# Nowboard.net
KiCad netlist of a schematic drawn in EAGLE
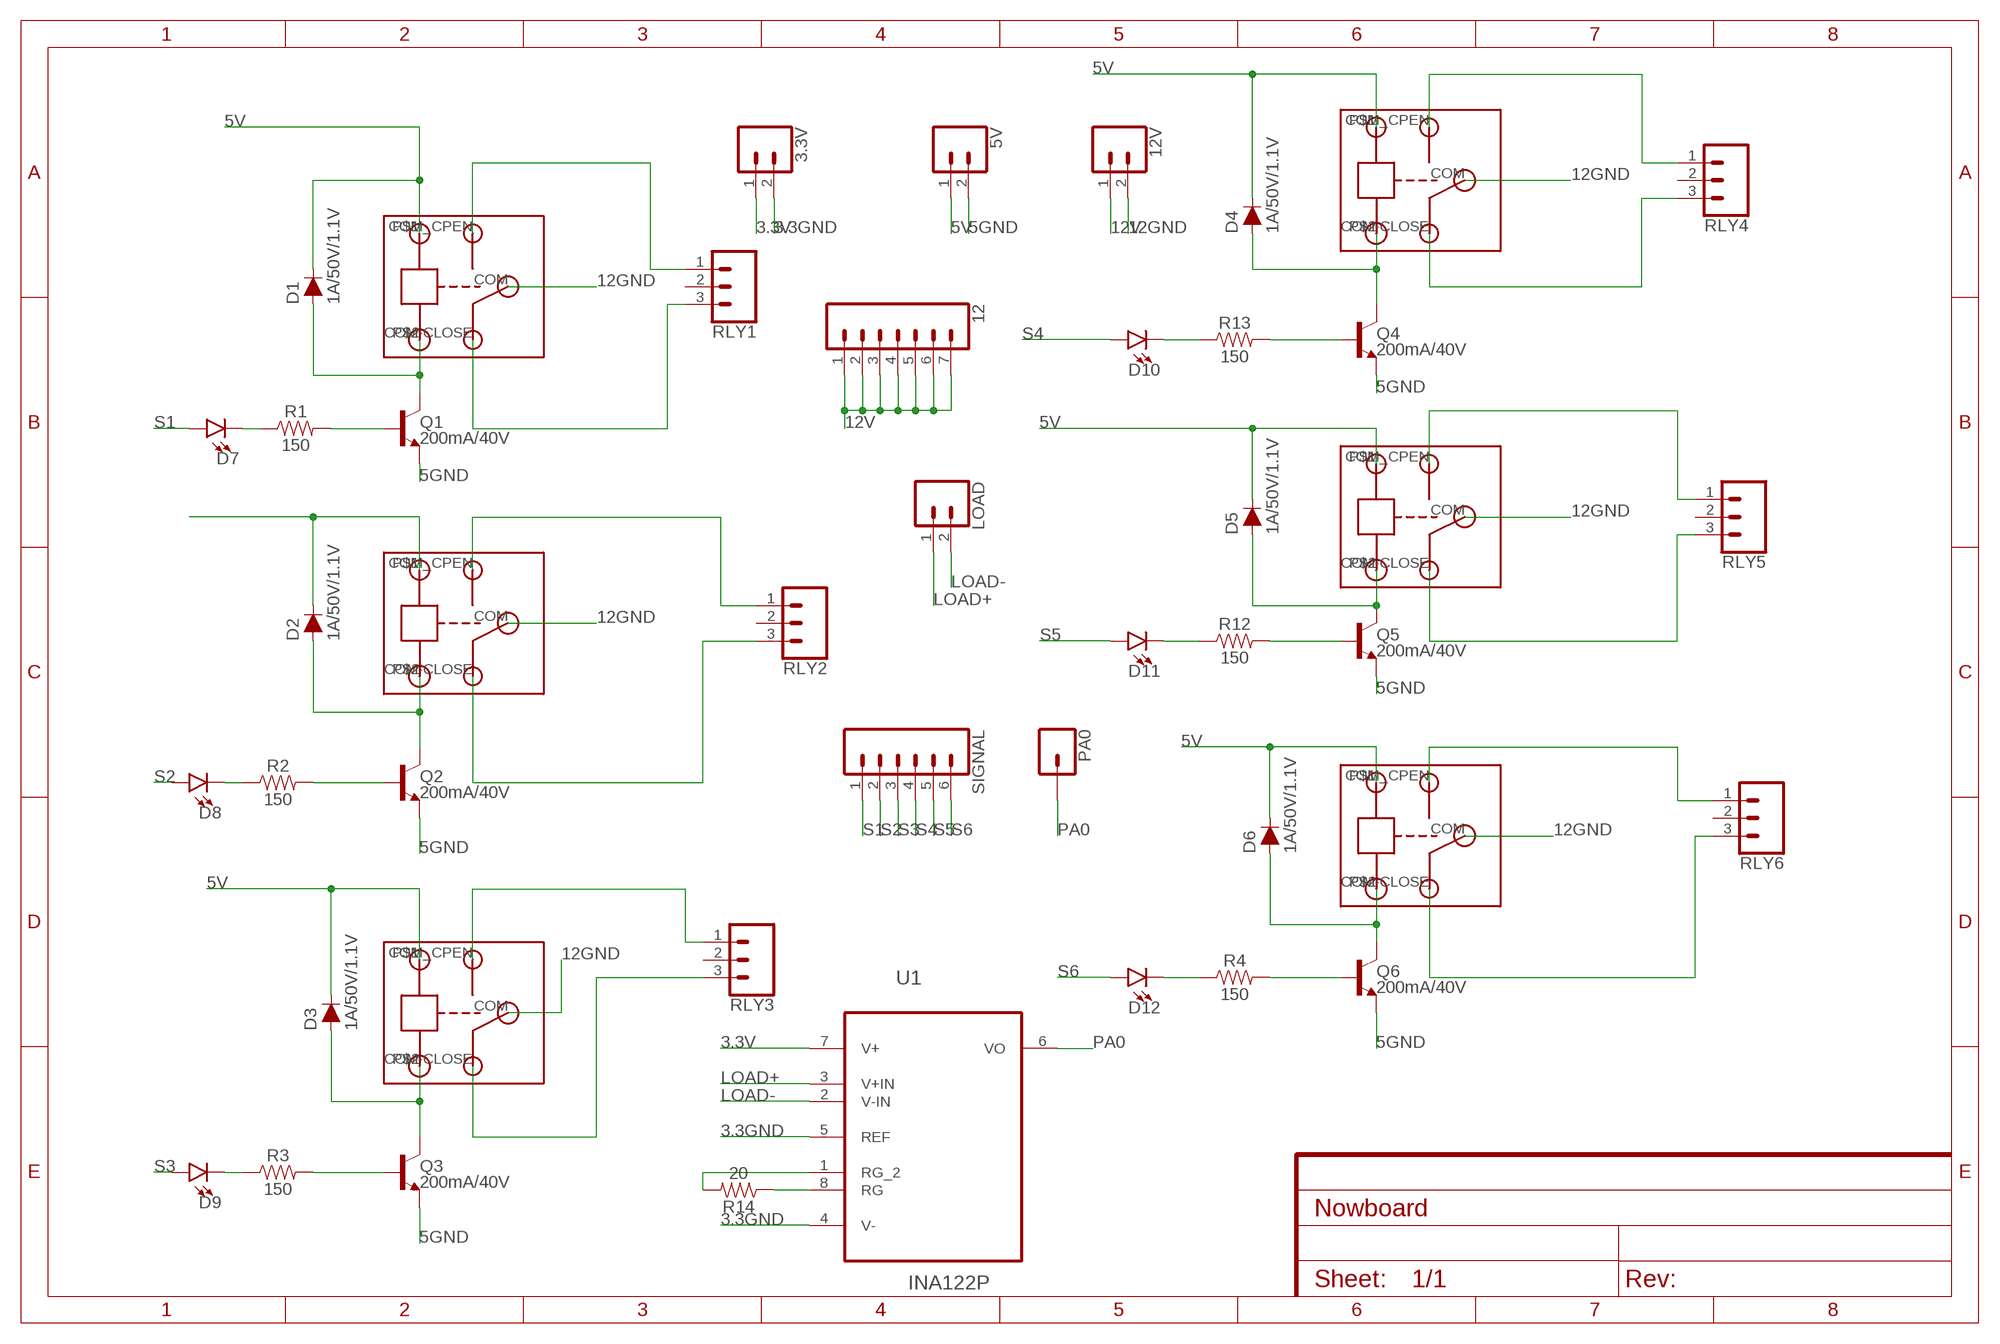
[diagram p0: schematic, sheet 1]

(export (version "E")
  (design (tool "Eeschema 10.0.6"))
  (components
    (comp (ref "3.3V")
      (value "CONN_02")
      (footprint "eagle-import:1X02")
      (libsource (lib "eagle-import") (part "CONN_02"))
    )
    (comp (ref "5V")
      (value "CONN_02")
      (footprint "eagle-import:1X02")
      (libsource (lib "eagle-import") (part "CONN_02"))
    )
    (comp (ref "12")
      (value "CONN_07")
      (footprint "eagle-import:1X07")
      (libsource (lib "eagle-import") (part "CONN_07"))
    )
    (comp (ref "12V")
      (value "CONN_02")
      (footprint "eagle-import:1X02")
      (libsource (lib "eagle-import") (part "CONN_02"))
    )
    (comp (ref "D1")
      (value "1A/50V/1.1V")
      (footprint "eagle-import:DIODE-1N4001")
      (libsource (lib "eagle-import") (part "DIODE-PTH"))
    )
    (comp (ref "D2")
      (value "1A/50V/1.1V")
      (footprint "eagle-import:DIODE-1N4001")
      (libsource (lib "eagle-import") (part "DIODE-PTH"))
    )
    (comp (ref "D3")
      (value "1A/50V/1.1V")
      (footprint "eagle-import:DIODE-1N4001")
      (libsource (lib "eagle-import") (part "DIODE-PTH"))
    )
    (comp (ref "D4")
      (value "1A/50V/1.1V")
      (footprint "eagle-import:DIODE-1N4001")
      (libsource (lib "eagle-import") (part "DIODE-PTH"))
    )
    (comp (ref "D5")
      (value "1A/50V/1.1V")
      (footprint "eagle-import:DIODE-1N4001")
      (libsource (lib "eagle-import") (part "DIODE-PTH"))
    )
    (comp (ref "D6")
      (value "1A/50V/1.1V")
      (footprint "eagle-import:DIODE-1N4001")
      (libsource (lib "eagle-import") (part "DIODE-PTH"))
    )
    (comp (ref "D7")
      (value "LED3MM")
      (footprint "eagle-import:LED_3MM")
      (libsource (lib "eagle-import") (part "LED3MM"))
    )
    (comp (ref "D8")
      (value "LED3MM")
      (footprint "eagle-import:LED_3MM")
      (libsource (lib "eagle-import") (part "LED3MM"))
    )
    (comp (ref "D9")
      (value "LED3MM")
      (footprint "eagle-import:LED_3MM")
      (libsource (lib "eagle-import") (part "LED3MM"))
    )
    (comp (ref "D10")
      (value "LED3MM")
      (footprint "eagle-import:LED_3MM")
      (libsource (lib "eagle-import") (part "LED3MM"))
    )
    (comp (ref "D11")
      (value "LED3MM")
      (footprint "eagle-import:LED_3MM")
      (libsource (lib "eagle-import") (part "LED3MM"))
    )
    (comp (ref "D12")
      (value "LED3MM")
      (footprint "eagle-import:LED_3MM")
      (libsource (lib "eagle-import") (part "LED3MM"))
    )
    (comp (ref "LOAD")
      (value "CONN_02")
      (footprint "eagle-import:1X02")
      (libsource (lib "eagle-import") (part "CONN_02"))
    )
    (comp (ref "PA0")
      (value "CONN_01")
      (footprint "eagle-import:1X01")
      (libsource (lib "eagle-import") (part "CONN_01"))
    )
    (comp (ref "Q1")
      (value "200mA/40V")
      (footprint "eagle-import:TO-92")
      (libsource (lib "eagle-import") (part "TRANS_NPN-2N3904"))
    )
    (comp (ref "Q2")
      (value "200mA/40V")
      (footprint "eagle-import:TO-92")
      (libsource (lib "eagle-import") (part "TRANS_NPN-2N3904"))
    )
    (comp (ref "Q3")
      (value "200mA/40V")
      (footprint "eagle-import:TO-92")
      (libsource (lib "eagle-import") (part "TRANS_NPN-2N3904"))
    )
    (comp (ref "Q4")
      (value "200mA/40V")
      (footprint "eagle-import:TO-92")
      (libsource (lib "eagle-import") (part "TRANS_NPN-2N3904"))
    )
    (comp (ref "Q5")
      (value "200mA/40V")
      (footprint "eagle-import:TO-92")
      (libsource (lib "eagle-import") (part "TRANS_NPN-2N3904"))
    )
    (comp (ref "Q6")
      (value "200mA/40V")
      (footprint "eagle-import:TO-92")
      (libsource (lib "eagle-import") (part "TRANS_NPN-2N3904"))
    )
    (comp (ref "R1")
      (value "150")
      (footprint "eagle-import:0603")
      (libsource (lib "eagle-import") (part "150OHM-0603-1/10W-1%"))
    )
    (comp (ref "R2")
      (value "150")
      (footprint "eagle-import:0603")
      (libsource (lib "eagle-import") (part "150OHM-0603-1/10W-1%"))
    )
    (comp (ref "R3")
      (value "150")
      (footprint "eagle-import:0603")
      (libsource (lib "eagle-import") (part "150OHM-0603-1/10W-1%"))
    )
    (comp (ref "R4")
      (value "150")
      (footprint "eagle-import:0603")
      (libsource (lib "eagle-import") (part "150OHM-0603-1/10W-1%"))
    )
    (comp (ref "R12")
      (value "150")
      (footprint "eagle-import:0603")
      (libsource (lib "eagle-import") (part "150OHM-0603-1/10W-1%"))
    )
    (comp (ref "R13")
      (value "150")
      (footprint "eagle-import:0603")
      (libsource (lib "eagle-import") (part "150OHM-0603-1/10W-1%"))
    )
    (comp (ref "R14")
      (value "20")
      (footprint "eagle-import:0603")
      (libsource (lib "eagle-import") (part "22OHM-0603-1/10W-1%"))
    )
    (comp (ref "RELAY1")
      (value "RELAY")
      (footprint "eagle-import:RELAY")
      (libsource (lib "eagle-import") (part "RELAY"))
    )
    (comp (ref "RELAY2")
      (value "RELAY")
      (footprint "eagle-import:RELAY")
      (libsource (lib "eagle-import") (part "RELAY"))
    )
    (comp (ref "RELAY3")
      (value "RELAY")
      (footprint "eagle-import:RELAY")
      (libsource (lib "eagle-import") (part "RELAY"))
    )
    (comp (ref "RELAY4")
      (value "RELAY")
      (footprint "eagle-import:RELAY")
      (libsource (lib "eagle-import") (part "RELAY"))
    )
    (comp (ref "RELAY5")
      (value "RELAY")
      (footprint "eagle-import:RELAY")
      (libsource (lib "eagle-import") (part "RELAY"))
    )
    (comp (ref "RELAY6")
      (value "RELAY")
      (footprint "eagle-import:RELAY")
      (libsource (lib "eagle-import") (part "RELAY"))
    )
    (comp (ref "RLY1")
      (value "CONN_03")
      (footprint "eagle-import:1X03")
      (libsource (lib "eagle-import") (part "CONN_03"))
    )
    (comp (ref "RLY2")
      (value "CONN_03")
      (footprint "eagle-import:1X03")
      (libsource (lib "eagle-import") (part "CONN_03"))
    )
    (comp (ref "RLY3")
      (value "CONN_03")
      (footprint "eagle-import:1X03")
      (libsource (lib "eagle-import") (part "CONN_03"))
    )
    (comp (ref "RLY4")
      (value "CONN_03")
      (footprint "eagle-import:1X03")
      (libsource (lib "eagle-import") (part "CONN_03"))
    )
    (comp (ref "RLY5")
      (value "CONN_03")
      (footprint "eagle-import:1X03")
      (libsource (lib "eagle-import") (part "CONN_03"))
    )
    (comp (ref "RLY6")
      (value "CONN_03")
      (footprint "eagle-import:1X03")
      (libsource (lib "eagle-import") (part "CONN_03"))
    )
    (comp (ref "SIGNAL")
      (value "CONN_06NO_SILK_FEMALE_PTH")
      (footprint "eagle-import:1X06_NO_SILK")
      (libsource (lib "eagle-import") (part "CONN_06NO_SILK_FEMALE_PTH"))
    )
    (comp (ref "U1")
      (value "INA122P")
      (footprint "eagle-import:DIP254P762X508-8")
      (fields (field (name "MF") "Texas Instruments"))
      (libsource (lib "eagle-import") (part "INA122P"))
    )
  )
  (nets
    (net (code "1") (name "/3.3GND") (class "Default")
      (node (ref "3.3V") (pin "2") (pinfunction "2_2") (pintype "passive"))
      (node (ref "U1") (pin "4") (pinfunction "V-_4") (pintype "power_in"))
      (node (ref "U1") (pin "5") (pinfunction "REF_5") (pintype "passive"))
    )
    (net (code "2") (name "/3.3V") (class "Default")
      (node (ref "3.3V") (pin "1") (pinfunction "1_1") (pintype "passive"))
      (node (ref "U1") (pin "7") (pinfunction "V+_7") (pintype "power_in"))
    )
    (net (code "3") (name "/5GND") (class "Default")
      (node (ref "5V") (pin "2") (pinfunction "2_2") (pintype "passive"))
      (node (ref "Q1") (pin "1") (pinfunction "E_1") (pintype "passive"))
      (node (ref "Q2") (pin "1") (pinfunction "E_1") (pintype "passive"))
      (node (ref "Q3") (pin "1") (pinfunction "E_1") (pintype "passive"))
      (node (ref "Q4") (pin "1") (pinfunction "E_1") (pintype "passive"))
      (node (ref "Q5") (pin "1") (pinfunction "E_1") (pintype "passive"))
      (node (ref "Q6") (pin "1") (pinfunction "E_1") (pintype "passive"))
    )
    (net (code "4") (name "/5V") (class "Default")
      (node (ref "5V") (pin "1") (pinfunction "1_1") (pintype "passive"))
      (node (ref "D1") (pin "C") (pinfunction "C_C") (pintype "passive"))
      (node (ref "D3") (pin "C") (pinfunction "C_C") (pintype "passive"))
      (node (ref "D4") (pin "C") (pinfunction "C_C") (pintype "passive"))
      (node (ref "D5") (pin "C") (pinfunction "C_C") (pintype "passive"))
      (node (ref "D6") (pin "C") (pinfunction "C_C") (pintype "passive"))
      (node (ref "RELAY1") (pin "P$1") (pinfunction "IN_P$1") (pintype "bidirectional"))
      (node (ref "RELAY3") (pin "P$1") (pinfunction "IN_P$1") (pintype "bidirectional"))
      (node (ref "RELAY4") (pin "P$1") (pinfunction "IN_P$1") (pintype "bidirectional"))
      (node (ref "RELAY5") (pin "P$1") (pinfunction "IN_P$1") (pintype "bidirectional"))
      (node (ref "RELAY6") (pin "P$1") (pinfunction "IN_P$1") (pintype "bidirectional"))
    )
    (net (code "5") (name "/12GND") (class "Default")
      (node (ref "12V") (pin "2") (pinfunction "2_2") (pintype "passive"))
      (node (ref "RELAY1") (pin "COM") (pinfunction "COM_COM") (pintype "bidirectional"))
      (node (ref "RELAY2") (pin "COM") (pinfunction "COM_COM") (pintype "bidirectional"))
      (node (ref "RELAY3") (pin "COM") (pinfunction "COM_COM") (pintype "bidirectional"))
      (node (ref "RELAY4") (pin "COM") (pinfunction "COM_COM") (pintype "bidirectional"))
      (node (ref "RELAY5") (pin "COM") (pinfunction "COM_COM") (pintype "bidirectional"))
      (node (ref "RELAY6") (pin "COM") (pinfunction "COM_COM") (pintype "bidirectional"))
    )
    (net (code "6") (name "/12V") (class "Default")
      (node (ref "12") (pin "1") (pinfunction "1_1") (pintype "passive"))
      (node (ref "12") (pin "2") (pinfunction "2_2") (pintype "passive"))
      (node (ref "12") (pin "3") (pinfunction "3_3") (pintype "passive"))
      (node (ref "12") (pin "4") (pinfunction "4_4") (pintype "passive"))
      (node (ref "12") (pin "5") (pinfunction "5_5") (pintype "passive"))
      (node (ref "12") (pin "6") (pinfunction "6_6") (pintype "passive"))
      (node (ref "12") (pin "7") (pinfunction "7_7") (pintype "passive"))
      (node (ref "12V") (pin "1") (pinfunction "1_1") (pintype "passive"))
    )
    (net (code "7") (name "/LOAD+") (class "Default")
      (node (ref "LOAD") (pin "1") (pinfunction "1_1") (pintype "passive"))
      (node (ref "U1") (pin "3") (pinfunction "V+IN_3") (pintype "input"))
    )
    (net (code "8") (name "/LOAD-") (class "Default")
      (node (ref "LOAD") (pin "2") (pinfunction "2_2") (pintype "passive"))
      (node (ref "U1") (pin "2") (pinfunction "V-IN_2") (pintype "input"))
    )
    (net (code "9") (name "/PA0") (class "Default")
      (node (ref "PA0") (pin "1") (pinfunction "1_1") (pintype "passive"))
      (node (ref "U1") (pin "6") (pinfunction "VO_6") (pintype "output"))
    )
    (net (code "10") (name "/S1") (class "Default")
      (node (ref "D7") (pin "A") (pinfunction "A_A") (pintype "passive"))
      (node (ref "SIGNAL") (pin "1") (pinfunction "1_1") (pintype "passive"))
    )
    (net (code "11") (name "/S2") (class "Default")
      (node (ref "D8") (pin "A") (pinfunction "A_A") (pintype "passive"))
      (node (ref "SIGNAL") (pin "2") (pinfunction "2_2") (pintype "passive"))
    )
    (net (code "12") (name "/S3") (class "Default")
      (node (ref "D9") (pin "A") (pinfunction "A_A") (pintype "passive"))
      (node (ref "SIGNAL") (pin "3") (pinfunction "3_3") (pintype "passive"))
    )
    (net (code "13") (name "/S4") (class "Default")
      (node (ref "D10") (pin "A") (pinfunction "A_A") (pintype "passive"))
      (node (ref "SIGNAL") (pin "4") (pinfunction "4_4") (pintype "passive"))
    )
    (net (code "14") (name "/S5") (class "Default")
      (node (ref "D11") (pin "A") (pinfunction "A_A") (pintype "passive"))
      (node (ref "SIGNAL") (pin "5") (pinfunction "5_5") (pintype "passive"))
    )
    (net (code "15") (name "/S6") (class "Default")
      (node (ref "D12") (pin "A") (pinfunction "A_A") (pintype "passive"))
      (node (ref "SIGNAL") (pin "6") (pinfunction "6_6") (pintype "passive"))
    )
    (net (code "16") (name "Net-(D7-C)") (class "Default")
      (node (ref "D7") (pin "K") (pinfunction "C_K") (pintype "passive"))
      (node (ref "R1") (pin "1") (pinfunction "1_1") (pintype "passive"))
    )
    (net (code "17") (name "Net-(D8-C)") (class "Default")
      (node (ref "D8") (pin "K") (pinfunction "C_K") (pintype "passive"))
      (node (ref "R2") (pin "1") (pinfunction "1_1") (pintype "passive"))
    )
    (net (code "18") (name "Net-(D9-C)") (class "Default")
      (node (ref "D9") (pin "K") (pinfunction "C_K") (pintype "passive"))
      (node (ref "R3") (pin "1") (pinfunction "1_1") (pintype "passive"))
    )
    (net (code "19") (name "Net-(D10-C)") (class "Default")
      (node (ref "D10") (pin "K") (pinfunction "C_K") (pintype "passive"))
      (node (ref "R13") (pin "1") (pinfunction "1_1") (pintype "passive"))
    )
    (net (code "20") (name "Net-(D11-C)") (class "Default")
      (node (ref "D11") (pin "K") (pinfunction "C_K") (pintype "passive"))
      (node (ref "R12") (pin "1") (pinfunction "1_1") (pintype "passive"))
    )
    (net (code "21") (name "Net-(D12-C)") (class "Default")
      (node (ref "D12") (pin "K") (pinfunction "C_K") (pintype "passive"))
      (node (ref "R4") (pin "1") (pinfunction "1_1") (pintype "passive"))
    )
    (net (code "22") (name "Net-(Q1-B)") (class "Default")
      (node (ref "Q1") (pin "2") (pinfunction "B_2") (pintype "passive"))
      (node (ref "R1") (pin "2") (pinfunction "2_2") (pintype "passive"))
    )
    (net (code "23") (name "Net-(Q1-C)") (class "Default")
      (node (ref "D1") (pin "A") (pinfunction "A_A") (pintype "passive"))
      (node (ref "Q1") (pin "3") (pinfunction "C_3") (pintype "passive"))
      (node (ref "RELAY1") (pin "P$2") (pinfunction "GND_P$2") (pintype "bidirectional"))
    )
    (net (code "24") (name "Net-(Q2-B)") (class "Default")
      (node (ref "Q2") (pin "2") (pinfunction "B_2") (pintype "passive"))
      (node (ref "R2") (pin "2") (pinfunction "2_2") (pintype "passive"))
    )
    (net (code "25") (name "Net-(Q2-C)") (class "Default")
      (node (ref "D2") (pin "A") (pinfunction "A_A") (pintype "passive"))
      (node (ref "Q2") (pin "3") (pinfunction "C_3") (pintype "passive"))
      (node (ref "RELAY2") (pin "P$2") (pinfunction "GND_P$2") (pintype "bidirectional"))
    )
    (net (code "26") (name "Net-(Q3-B)") (class "Default")
      (node (ref "Q3") (pin "2") (pinfunction "B_2") (pintype "passive"))
      (node (ref "R3") (pin "2") (pinfunction "2_2") (pintype "passive"))
    )
    (net (code "27") (name "Net-(Q3-C)") (class "Default")
      (node (ref "D3") (pin "A") (pinfunction "A_A") (pintype "passive"))
      (node (ref "Q3") (pin "3") (pinfunction "C_3") (pintype "passive"))
      (node (ref "RELAY3") (pin "P$2") (pinfunction "GND_P$2") (pintype "bidirectional"))
    )
    (net (code "28") (name "Net-(Q4-B)") (class "Default")
      (node (ref "Q4") (pin "2") (pinfunction "B_2") (pintype "passive"))
      (node (ref "R13") (pin "2") (pinfunction "2_2") (pintype "passive"))
    )
    (net (code "29") (name "Net-(Q4-C)") (class "Default")
      (node (ref "D4") (pin "A") (pinfunction "A_A") (pintype "passive"))
      (node (ref "Q4") (pin "3") (pinfunction "C_3") (pintype "passive"))
      (node (ref "RELAY4") (pin "P$2") (pinfunction "GND_P$2") (pintype "bidirectional"))
    )
    (net (code "30") (name "Net-(Q5-B)") (class "Default")
      (node (ref "Q5") (pin "2") (pinfunction "B_2") (pintype "passive"))
      (node (ref "R12") (pin "2") (pinfunction "2_2") (pintype "passive"))
    )
    (net (code "31") (name "Net-(Q5-C)") (class "Default")
      (node (ref "D5") (pin "A") (pinfunction "A_A") (pintype "passive"))
      (node (ref "Q5") (pin "3") (pinfunction "C_3") (pintype "passive"))
      (node (ref "RELAY5") (pin "P$2") (pinfunction "GND_P$2") (pintype "bidirectional"))
    )
    (net (code "32") (name "Net-(Q6-B)") (class "Default")
      (node (ref "Q6") (pin "2") (pinfunction "B_2") (pintype "passive"))
      (node (ref "R4") (pin "2") (pinfunction "2_2") (pintype "passive"))
    )
    (net (code "33") (name "Net-(Q6-C)") (class "Default")
      (node (ref "D6") (pin "A") (pinfunction "A_A") (pintype "passive"))
      (node (ref "Q6") (pin "3") (pinfunction "C_3") (pintype "passive"))
      (node (ref "RELAY6") (pin "P$2") (pinfunction "GND_P$2") (pintype "bidirectional"))
    )
    (net (code "34") (name "Net-(RELAY1-COM-OPEN)") (class "Default")
      (node (ref "RELAY1") (pin "COM_CPEN") (pinfunction "COM-OPEN_COM_CPEN") (pintype "bidirectional"))
      (node (ref "RLY1") (pin "1") (pinfunction "1_1") (pintype "passive"))
    )
    (net (code "35") (name "Net-(RELAY1-PadCOM-CLOSE)") (class "Default")
      (node (ref "RELAY1") (pin "COM-CLOSE") (pinfunction "COM-CLOSE_COM-CLOSE") (pintype "bidirectional"))
      (node (ref "RLY1") (pin "3") (pinfunction "3_3") (pintype "passive"))
    )
    (net (code "36") (name "Net-(RELAY2-COM-OPEN)") (class "Default")
      (node (ref "RELAY2") (pin "COM_CPEN") (pinfunction "COM-OPEN_COM_CPEN") (pintype "bidirectional"))
      (node (ref "RLY2") (pin "1") (pinfunction "1_1") (pintype "passive"))
    )
    (net (code "37") (name "Net-(RELAY2-IN)") (class "Default")
      (node (ref "D2") (pin "C") (pinfunction "C_C") (pintype "passive"))
      (node (ref "RELAY2") (pin "P$1") (pinfunction "IN_P$1") (pintype "bidirectional"))
    )
    (net (code "38") (name "Net-(RELAY2-PadCOM-CLOSE)") (class "Default")
      (node (ref "RELAY2") (pin "COM-CLOSE") (pinfunction "COM-CLOSE_COM-CLOSE") (pintype "bidirectional"))
      (node (ref "RLY2") (pin "3") (pinfunction "3_3") (pintype "passive"))
    )
    (net (code "39") (name "Net-(RELAY3-COM-OPEN)") (class "Default")
      (node (ref "RELAY3") (pin "COM_CPEN") (pinfunction "COM-OPEN_COM_CPEN") (pintype "bidirectional"))
      (node (ref "RLY3") (pin "1") (pinfunction "1_1") (pintype "passive"))
    )
    (net (code "40") (name "Net-(RELAY3-PadCOM-CLOSE)") (class "Default")
      (node (ref "RELAY3") (pin "COM-CLOSE") (pinfunction "COM-CLOSE_COM-CLOSE") (pintype "bidirectional"))
      (node (ref "RLY3") (pin "3") (pinfunction "3_3") (pintype "passive"))
    )
    (net (code "41") (name "Net-(RELAY4-COM-OPEN)") (class "Default")
      (node (ref "RELAY4") (pin "COM_CPEN") (pinfunction "COM-OPEN_COM_CPEN") (pintype "bidirectional"))
      (node (ref "RLY4") (pin "1") (pinfunction "1_1") (pintype "passive"))
    )
    (net (code "42") (name "Net-(RELAY4-PadCOM-CLOSE)") (class "Default")
      (node (ref "RELAY4") (pin "COM-CLOSE") (pinfunction "COM-CLOSE_COM-CLOSE") (pintype "bidirectional"))
      (node (ref "RLY4") (pin "3") (pinfunction "3_3") (pintype "passive"))
    )
    (net (code "43") (name "Net-(RELAY5-COM-OPEN)") (class "Default")
      (node (ref "RELAY5") (pin "COM_CPEN") (pinfunction "COM-OPEN_COM_CPEN") (pintype "bidirectional"))
      (node (ref "RLY5") (pin "1") (pinfunction "1_1") (pintype "passive"))
    )
    (net (code "44") (name "Net-(RELAY5-PadCOM-CLOSE)") (class "Default")
      (node (ref "RELAY5") (pin "COM-CLOSE") (pinfunction "COM-CLOSE_COM-CLOSE") (pintype "bidirectional"))
      (node (ref "RLY5") (pin "3") (pinfunction "3_3") (pintype "passive"))
    )
    (net (code "45") (name "Net-(RELAY6-COM-OPEN)") (class "Default")
      (node (ref "RELAY6") (pin "COM_CPEN") (pinfunction "COM-OPEN_COM_CPEN") (pintype "bidirectional"))
      (node (ref "RLY6") (pin "1") (pinfunction "1_1") (pintype "passive"))
    )
    (net (code "46") (name "Net-(RELAY6-PadCOM-CLOSE)") (class "Default")
      (node (ref "RELAY6") (pin "COM-CLOSE") (pinfunction "COM-CLOSE_COM-CLOSE") (pintype "bidirectional"))
      (node (ref "RLY6") (pin "3") (pinfunction "3_3") (pintype "passive"))
    )
    (net (code "47") (name "Net-(U1-RG)") (class "Default")
      (node (ref "R14") (pin "1") (pinfunction "1_1") (pintype "passive"))
      (node (ref "U1") (pin "8") (pinfunction "RG_8") (pintype "passive"))
    )
    (net (code "48") (name "Net-(U1-RG_2)") (class "Default")
      (node (ref "R14") (pin "2") (pinfunction "2_2") (pintype "passive"))
      (node (ref "U1") (pin "1") (pinfunction "RG_2_1") (pintype "passive"))
    )
    (net (code "49") (name "unconnected-(RLY1-Pad2)") (class "Default")
      (node (ref "RLY1") (pin "2") (pinfunction "2_2") (pintype "passive"))
    )
    (net (code "50") (name "unconnected-(RLY2-Pad2)") (class "Default")
      (node (ref "RLY2") (pin "2") (pinfunction "2_2") (pintype "passive"))
    )
    (net (code "51") (name "unconnected-(RLY3-Pad2)") (class "Default")
      (node (ref "RLY3") (pin "2") (pinfunction "2_2") (pintype "passive"))
    )
    (net (code "52") (name "unconnected-(RLY4-Pad2)") (class "Default")
      (node (ref "RLY4") (pin "2") (pinfunction "2_2") (pintype "passive"))
    )
    (net (code "53") (name "unconnected-(RLY5-Pad2)") (class "Default")
      (node (ref "RLY5") (pin "2") (pinfunction "2_2") (pintype "passive"))
    )
    (net (code "54") (name "unconnected-(RLY6-Pad2)") (class "Default")
      (node (ref "RLY6") (pin "2") (pinfunction "2_2") (pintype "passive"))
    )
  )
)
